# 3G4G.net
KiCad netlist of a schematic drawn in Altium Designer
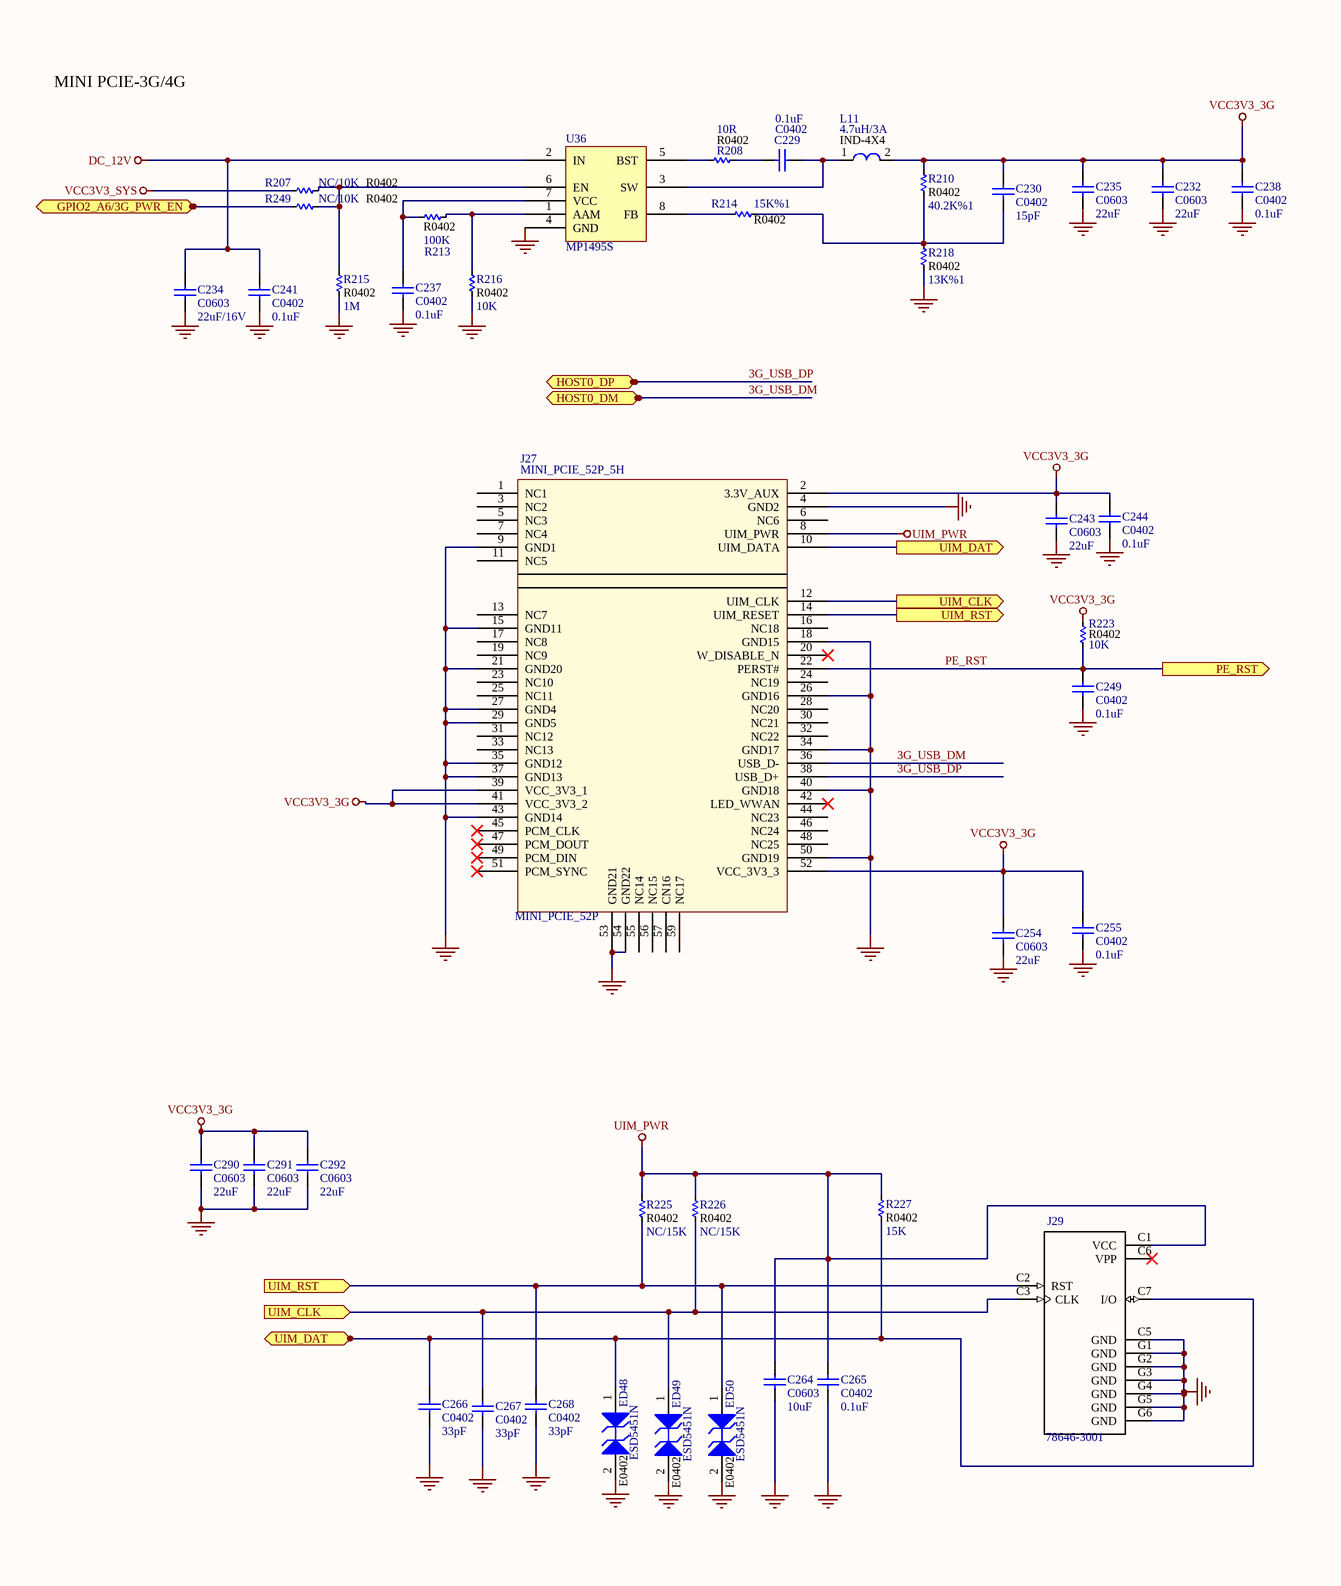
[diagram p0: 3G4G.SchDoc, left]
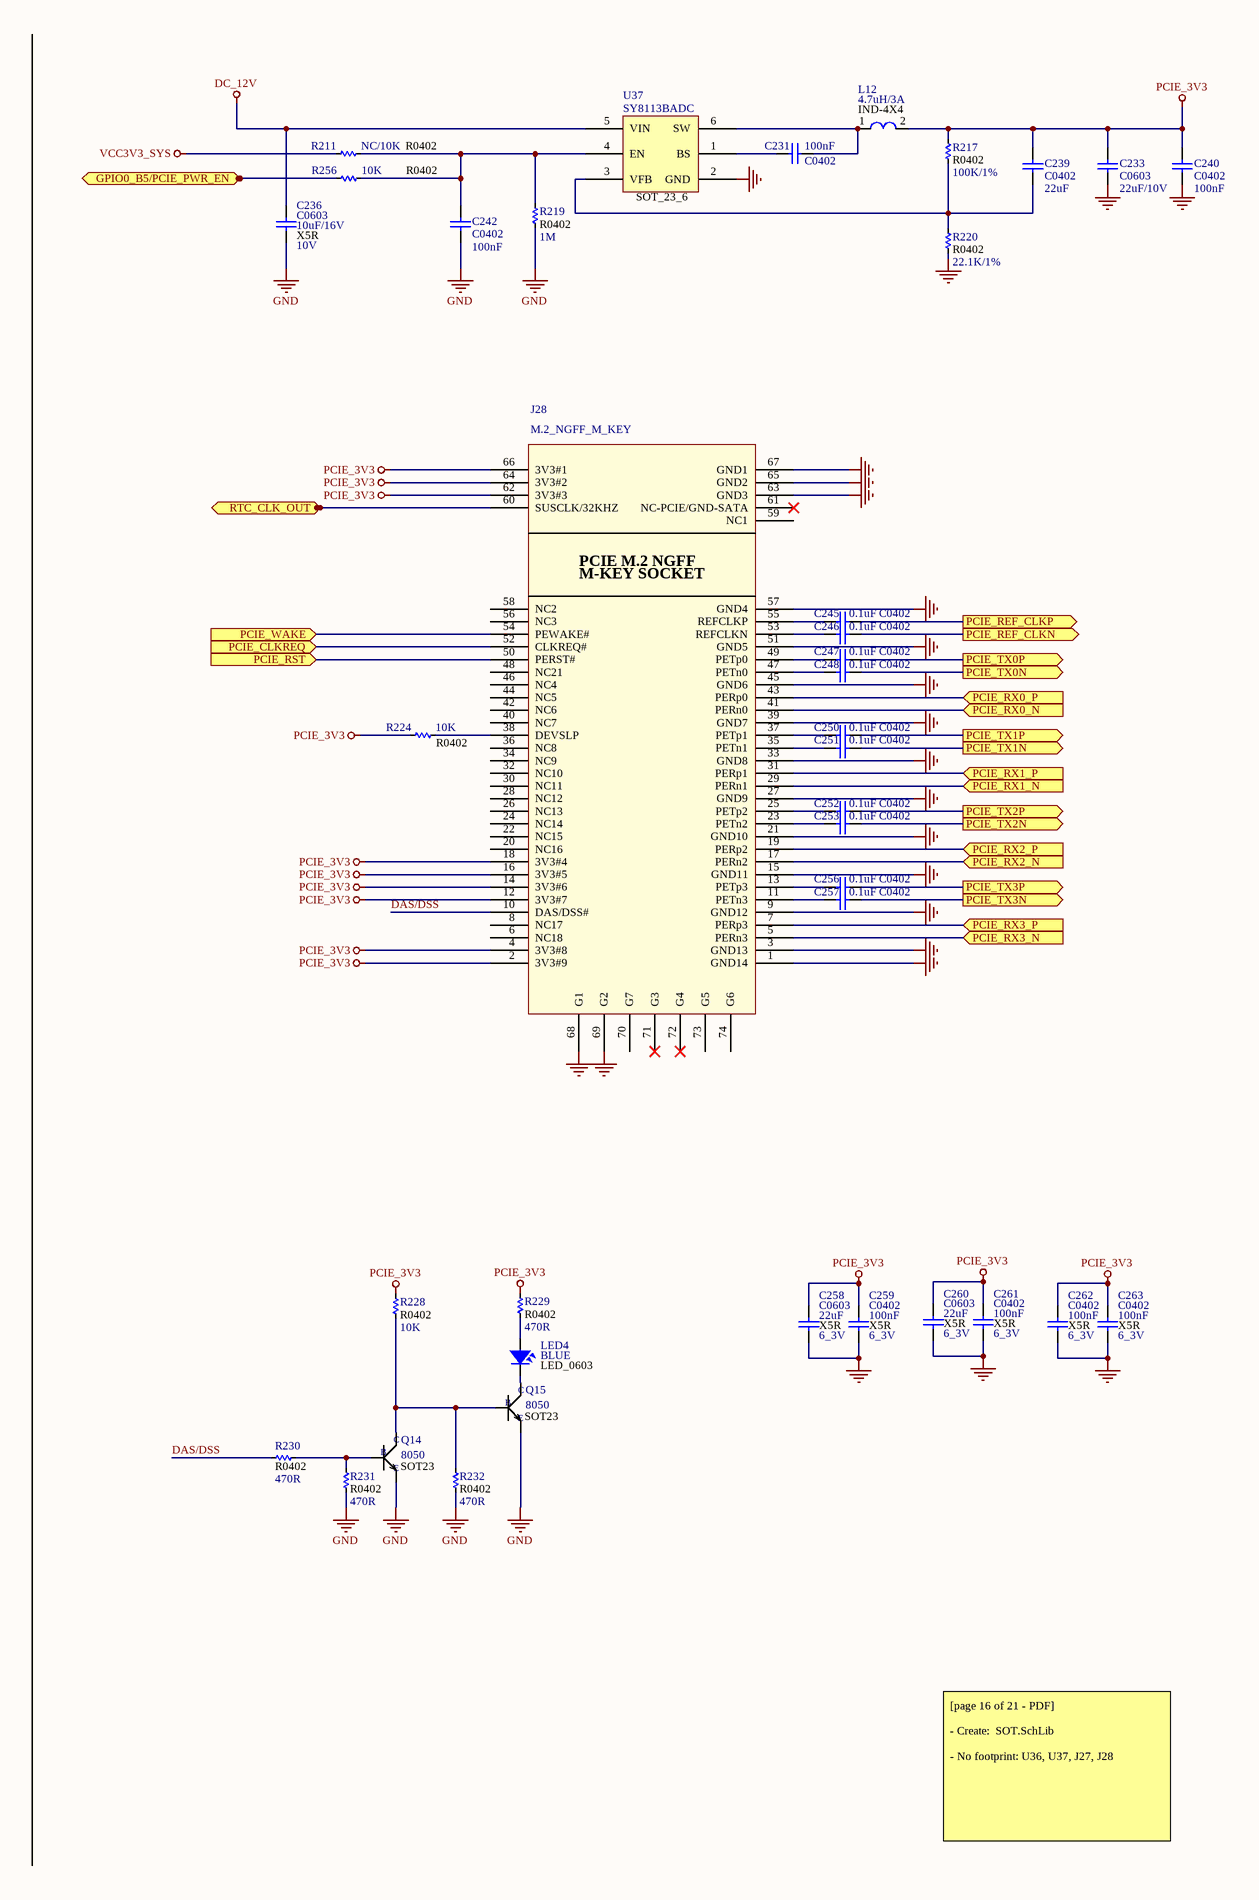
[diagram p1: 3G4G.SchDoc, right]

(export (version "E")
  (design (tool "Eeschema 10.0.6"))
  (components
    (comp (ref "C229")
      (value "C0402")
      (footprint "C 0402")
      (description "Capacitor")
      (fields (field (name "ALTIUM_VALUE") "0.1uF"))
      (libsource (lib "Miscellaneous Devices") (part "Cap"))
    )
    (comp (ref "C230")
      (value "C0402")
      (footprint "C 0402")
      (description "Capacitor")
      (fields (field (name "ALTIUM_VALUE") "15pF"))
      (libsource (lib "Miscellaneous Devices") (part "Cap"))
    )
    (comp (ref "C231")
      (value "C0402")
      (footprint "C 0402")
      (description "Capacitor")
      (fields (field (name "ALTIUM_VALUE") "100nF"))
      (libsource (lib "Miscellaneous Devices") (part "Cap"))
    )
    (comp (ref "C232")
      (value "C0603")
      (footprint "C 0603")
      (description "Capacitor")
      (fields (field (name "ALTIUM_VALUE") "22uF"))
      (libsource (lib "Miscellaneous Devices") (part "Cap"))
    )
    (comp (ref "C233")
      (value "C0603")
      (footprint "C 0603")
      (description "Capacitor")
      (fields (field (name "ALTIUM_VALUE") "22uF/10V"))
      (libsource (lib "Miscellaneous Devices") (part "Cap"))
    )
    (comp (ref "C234")
      (value "C0603")
      (footprint "C 0603")
      (description "Capacitor")
      (fields (field (name "ALTIUM_VALUE") "22uF/16V"))
      (libsource (lib "Miscellaneous Devices") (part "Cap"))
    )
    (comp (ref "C235")
      (value "C0603")
      (footprint "C 0603")
      (description "Capacitor")
      (fields (field (name "ALTIUM_VALUE") "22uF"))
      (libsource (lib "Miscellaneous Devices") (part "Cap"))
    )
    (comp (ref "C236")
      (value "C0603")
      (footprint "C 0603")
      (description "Capacitor")
      (fields
        (field (name "ALTIUM_VALUE") "10uF/16V")
        (field (name "ALTIUM_UNNAMED_1") "X5R")
        (field (name "ALTIUM_UNNAMED_2") "10V")
      )
      (libsource (lib "Miscellaneous Devices") (part "Cap"))
    )
    (comp (ref "C237")
      (value "C0402")
      (footprint "C 0402")
      (description "Capacitor")
      (fields (field (name "ALTIUM_VALUE") "0.1uF"))
      (libsource (lib "Miscellaneous Devices") (part "Cap"))
    )
    (comp (ref "C238")
      (value "C0402")
      (footprint "C 0402")
      (description "Capacitor")
      (fields (field (name "ALTIUM_VALUE") "0.1uF"))
      (libsource (lib "Miscellaneous Devices") (part "Cap"))
    )
    (comp (ref "C239")
      (value "C0402")
      (footprint "C 0402")
      (description "Capacitor")
      (fields (field (name "ALTIUM_VALUE") "22uF"))
      (libsource (lib "Miscellaneous Devices") (part "Cap"))
    )
    (comp (ref "C240")
      (value "C0402")
      (footprint "C 0402")
      (description "Capacitor")
      (fields (field (name "ALTIUM_VALUE") "100nF"))
      (libsource (lib "Miscellaneous Devices") (part "Cap"))
    )
    (comp (ref "C241")
      (value "C0402")
      (footprint "C 0402")
      (description "Capacitor")
      (fields (field (name "ALTIUM_VALUE") "0.1uF"))
      (libsource (lib "Miscellaneous Devices") (part "Cap"))
    )
    (comp (ref "C242")
      (value "C0402")
      (footprint "C 0402")
      (description "Capacitor")
      (fields (field (name "ALTIUM_VALUE") "100nF"))
      (libsource (lib "Miscellaneous Devices") (part "Cap"))
    )
    (comp (ref "C243")
      (value "C0603")
      (footprint "C 0603")
      (description "Capacitor")
      (fields (field (name "ALTIUM_VALUE") "22uF"))
      (libsource (lib "Miscellaneous Devices") (part "Cap"))
    )
    (comp (ref "C244")
      (value "C0402")
      (footprint "C 0402")
      (description "Capacitor")
      (fields (field (name "ALTIUM_VALUE") "0.1uF"))
      (libsource (lib "Miscellaneous Devices") (part "Cap"))
    )
    (comp (ref "C245")
      (value "C0402")
      (footprint "C 0402")
      (description "Capacitor")
      (fields (field (name "ALTIUM_VALUE") "0.1uF"))
      (libsource (lib "Miscellaneous Devices") (part "Cap"))
    )
    (comp (ref "C246")
      (value "C0402")
      (footprint "C 0402")
      (description "Capacitor")
      (fields (field (name "ALTIUM_VALUE") "0.1uF"))
      (libsource (lib "Miscellaneous Devices") (part "Cap"))
    )
    (comp (ref "C247")
      (value "C0402")
      (footprint "C 0402")
      (description "Capacitor")
      (fields (field (name "ALTIUM_VALUE") "0.1uF"))
      (libsource (lib "Miscellaneous Devices") (part "Cap"))
    )
    (comp (ref "C248")
      (value "C0402")
      (footprint "C 0402")
      (description "Capacitor")
      (fields (field (name "ALTIUM_VALUE") "0.1uF"))
      (libsource (lib "Miscellaneous Devices") (part "Cap"))
    )
    (comp (ref "C249")
      (value "C0402")
      (footprint "C 0402")
      (description "Capacitor")
      (fields (field (name "ALTIUM_VALUE") "0.1uF"))
      (libsource (lib "Miscellaneous Devices") (part "Cap"))
    )
    (comp (ref "C250")
      (value "C0402")
      (footprint "C 0402")
      (description "Capacitor")
      (fields (field (name "ALTIUM_VALUE") "0.1uF"))
      (libsource (lib "Miscellaneous Devices") (part "Cap"))
    )
    (comp (ref "C251")
      (value "C0402")
      (footprint "C 0402")
      (description "Capacitor")
      (fields (field (name "ALTIUM_VALUE") "0.1uF"))
      (libsource (lib "Miscellaneous Devices") (part "Cap"))
    )
    (comp (ref "C252")
      (value "C0402")
      (footprint "C 0402")
      (description "Capacitor")
      (fields (field (name "ALTIUM_VALUE") "0.1uF"))
      (libsource (lib "Miscellaneous Devices") (part "Cap"))
    )
    (comp (ref "C253")
      (value "C0402")
      (footprint "C 0402")
      (description "Capacitor")
      (fields (field (name "ALTIUM_VALUE") "0.1uF"))
      (libsource (lib "Miscellaneous Devices") (part "Cap"))
    )
    (comp (ref "C254")
      (value "C0603")
      (footprint "C 0603")
      (description "Capacitor")
      (fields (field (name "ALTIUM_VALUE") "22uF"))
      (libsource (lib "Miscellaneous Devices") (part "Cap"))
    )
    (comp (ref "C255")
      (value "C0402")
      (footprint "C 0402")
      (description "Capacitor")
      (fields (field (name "ALTIUM_VALUE") "0.1uF"))
      (libsource (lib "Miscellaneous Devices") (part "Cap"))
    )
    (comp (ref "C256")
      (value "C0402")
      (footprint "C 0402")
      (description "Capacitor")
      (fields (field (name "ALTIUM_VALUE") "0.1uF"))
      (libsource (lib "Miscellaneous Devices") (part "Cap"))
    )
    (comp (ref "C257")
      (value "C0402")
      (footprint "C 0402")
      (description "Capacitor")
      (fields (field (name "ALTIUM_VALUE") "0.1uF"))
      (libsource (lib "Miscellaneous Devices") (part "Cap"))
    )
    (comp (ref "C258")
      (value "C0603")
      (footprint "C 0603")
      (description "Capacitor")
      (fields
        (field (name "ALTIUM_VALUE") "22uF")
        (field (name "ALTIUM_UNNAMED_1") "X5R")
        (field (name "ALTIUM_UNNAMED_2") "6_3V")
      )
      (libsource (lib "Miscellaneous Devices") (part "Cap"))
    )
    (comp (ref "C259")
      (value "C0402")
      (footprint "C 0402")
      (description "Capacitor")
      (fields
        (field (name "ALTIUM_VALUE") "100nF")
        (field (name "ALTIUM_UNNAMED_1") "X5R")
        (field (name "ALTIUM_UNNAMED_2") "6_3V")
      )
      (libsource (lib "Miscellaneous Devices") (part "Cap"))
    )
    (comp (ref "C260")
      (value "C0603")
      (footprint "C 0603")
      (description "Capacitor")
      (fields
        (field (name "ALTIUM_VALUE") "22uF")
        (field (name "ALTIUM_UNNAMED_1") "X5R")
        (field (name "ALTIUM_UNNAMED_2") "6_3V")
      )
      (libsource (lib "Miscellaneous Devices") (part "Cap"))
    )
    (comp (ref "C261")
      (value "C0402")
      (footprint "C 0402")
      (description "Capacitor")
      (fields
        (field (name "ALTIUM_VALUE") "100nF")
        (field (name "ALTIUM_UNNAMED_1") "X5R")
        (field (name "ALTIUM_UNNAMED_2") "6_3V")
      )
      (libsource (lib "Miscellaneous Devices") (part "Cap"))
    )
    (comp (ref "C262")
      (value "C0402")
      (footprint "C 0402")
      (description "Capacitor")
      (fields
        (field (name "ALTIUM_VALUE") "100nF")
        (field (name "ALTIUM_UNNAMED_1") "X5R")
        (field (name "ALTIUM_UNNAMED_2") "6_3V")
      )
      (libsource (lib "Miscellaneous Devices") (part "Cap"))
    )
    (comp (ref "C263")
      (value "C0402")
      (footprint "C 0402")
      (description "Capacitor")
      (fields
        (field (name "ALTIUM_VALUE") "100nF")
        (field (name "ALTIUM_UNNAMED_1") "X5R")
        (field (name "ALTIUM_UNNAMED_2") "6_3V")
      )
      (libsource (lib "Miscellaneous Devices") (part "Cap"))
    )
    (comp (ref "C264")
      (value "C0603")
      (footprint "C 0603")
      (description "Capacitor")
      (fields (field (name "ALTIUM_VALUE") "10uF"))
      (libsource (lib "Miscellaneous Devices") (part "Cap"))
    )
    (comp (ref "C265")
      (value "C0402")
      (footprint "C 0402")
      (description "Capacitor")
      (fields (field (name "ALTIUM_VALUE") "0.1uF"))
      (libsource (lib "Miscellaneous Devices") (part "Cap"))
    )
    (comp (ref "C266")
      (value "C0402")
      (footprint "C 0402")
      (description "Capacitor")
      (fields (field (name "ALTIUM_VALUE") "33pF"))
      (libsource (lib "Miscellaneous Devices") (part "Cap"))
    )
    (comp (ref "C267")
      (value "C0402")
      (footprint "C 0402")
      (description "Capacitor")
      (fields (field (name "ALTIUM_VALUE") "33pF"))
      (libsource (lib "Miscellaneous Devices") (part "Cap"))
    )
    (comp (ref "C268")
      (value "C0402")
      (footprint "C 0402")
      (description "Capacitor")
      (fields (field (name "ALTIUM_VALUE") "33pF"))
      (libsource (lib "Miscellaneous Devices") (part "Cap"))
    )
    (comp (ref "C290")
      (value "C0603")
      (footprint "C 0603")
      (description "Capacitor")
      (fields (field (name "ALTIUM_VALUE") "22uF"))
      (libsource (lib "Miscellaneous Devices") (part "Cap"))
    )
    (comp (ref "C291")
      (value "C0603")
      (footprint "C 0603")
      (description "Capacitor")
      (fields (field (name "ALTIUM_VALUE") "22uF"))
      (libsource (lib "Miscellaneous Devices") (part "Cap"))
    )
    (comp (ref "C292")
      (value "C0603")
      (footprint "C 0603")
      (description "Capacitor")
      (fields (field (name "ALTIUM_VALUE") "22uF"))
      (libsource (lib "Miscellaneous Devices") (part "Cap"))
    )
    (comp (ref "ED48")
      (value "ESD5451N")
      (footprint "DFN1006-2L")
      (description "600 W Peak Power Zener Transient Voltage Suppressor, Bidirectional, 2-Pin SMB, Tape and Reel")
      (fields
        (field (name "MANUFACTURER") "On Semiconductor")
        (field (name "PARTNUMBER") "1SMB54CAT3")
        (field (name "SIZE") "E0402")
      )
      (libsource (lib "ON Semi Transient Voltage Suppressors (TVS)") (part "1SMB54CAT3"))
    )
    (comp (ref "ED49")
      (value "ESD5451N")
      (footprint "DFN1006-2L")
      (description "600 W Peak Power Zener Transient Voltage Suppressor, Bidirectional, 2-Pin SMB, Tape and Reel")
      (fields
        (field (name "MANUFACTURER") "On Semiconductor")
        (field (name "PARTNUMBER") "1SMB54CAT3")
        (field (name "SIZE") "E0402")
      )
      (libsource (lib "ON Semi Transient Voltage Suppressors (TVS)") (part "1SMB54CAT3"))
    )
    (comp (ref "ED50")
      (value "ESD5451N")
      (footprint "DFN1006-2L")
      (description "600 W Peak Power Zener Transient Voltage Suppressor, Bidirectional, 2-Pin SMB, Tape and Reel")
      (fields
        (field (name "MANUFACTURER") "On Semiconductor")
        (field (name "PARTNUMBER") "1SMB54CAT3")
        (field (name "SIZE") "E0402")
      )
      (libsource (lib "ON Semi Transient Voltage Suppressors (TVS)") (part "1SMB54CAT3"))
    )
    (comp (ref "J27")
      (value "MINI_PCIE_52P_5H")
      (footprint "MINI_PCIE_52PIN")
      (fields (field (name "ALTIUM_UNNAMED_1") "MINI_PCIE_52P"))
      (libsource (lib "SOT") (part "MINI_PCIE_52P_5H"))
    )
    (comp (ref "J28")
      (value "M.2_NGFF_M_KEY")
      (footprint "*CONN_1-2199230-5_1-2199230-5(Primary)")
      (libsource (lib "SOT") (part "M.2_NGFF_M_KEY"))
    )
    (comp (ref "J29")
      (value "78646-3001")
      (footprint "*CONN_78646-3001_78646-3001(Primary)")
      (description "Conn Micro SIM Card SKT 6 POS 2.54mm Solder RA SMD 0.5A/Contact Embossed T/R")
      (fields (field (name "MF") "Molex"))
      (libsource (lib "78646-3001") (part "78646-3001"))
    )
    (comp (ref "L11")
      (value "4.7uH/3A")
      (footprint "L-SMD-M-7.3x4.5")
      (fields
        (field (name "PARTNO") "78477010")
        (field (name "MANUFACTURER") "Wurth Elektronik")
        (field (name "ALTIUM_UNNAMED_1") "IND-4X4")
      )
      (libsource (lib "LIBRARY") (part "L-SMD-1"))
    )
    (comp (ref "L12")
      (value "4.7uH/3A")
      (footprint "L-SMD-M-7.3x4.5")
      (fields
        (field (name "PARTNO") "78477010")
        (field (name "MANUFACTURER") "Wurth Elektronik")
        (field (name "ALTIUM_UNNAMED_1") "IND-4X4")
      )
      (libsource (lib "LIBRARY") (part "L-SMD-1"))
    )
    (comp (ref "LED4")
      (value "LED SMD")
      (footprint "SM-LED-0805-Blue")
      (fields (field (name "PACKAGE") "LED_0603") (field (name "COLOR") "BLUE"))
      (libsource (lib "syhaunguyen") (part "LED-SMD-0805"))
    )
    (comp (ref "Q14")
      (value "8050")
      (footprint "*SOT-23")
      (fields
        (field (name "MF") "Recom Power")
        (field (name "MP") "S8050")
        (field (name "ALTIUM_UNNAMED_1") "SOT23")
      )
      (libsource (lib "SMD-TRANSISTORS-NPN-25V-500MW_SOT-23_") (part "SMD-TRANSISTORS-NPN-25V-500MW(SOT-23)"))
    )
    (comp (ref "Q15")
      (value "8050")
      (footprint "*SOT-23")
      (fields
        (field (name "MF") "Recom Power")
        (field (name "MP") "S8050")
        (field (name "ALTIUM_UNNAMED_1") "SOT23")
      )
      (libsource (lib "SMD-TRANSISTORS-NPN-25V-500MW_SOT-23_") (part "SMD-TRANSISTORS-NPN-25V-500MW(SOT-23)"))
    )
    (comp (ref "R207")
      (value "R0402")
      (footprint "R 0402")
      (description "Resistor")
      (fields (field (name "MANUFACTURER") "Generic Components") (field (name "ALTIUM_VALUE") "NC/10K"))
      (libsource (lib "LIBRARY") (part "Res-SMD"))
    )
    (comp (ref "R208")
      (value "R0402")
      (footprint "R 0402")
      (description "Resistor")
      (fields (field (name "MANUFACTURER") "Generic Components") (field (name "ALTIUM_VALUE") "10R"))
      (libsource (lib "LIBRARY") (part "Res-SMD"))
    )
    (comp (ref "R210")
      (value "R0402")
      (footprint "R 0402")
      (description "Resistor")
      (fields (field (name "MANUFACTURER") "Generic Components") (field (name "ALTIUM_VALUE") "40.2K%1"))
      (libsource (lib "LIBRARY") (part "Res-SMD"))
    )
    (comp (ref "R211")
      (value "R0402")
      (footprint "R 0402")
      (description "Resistor")
      (fields (field (name "MANUFACTURER") "Generic Components") (field (name "ALTIUM_VALUE") "NC/10K"))
      (libsource (lib "LIBRARY") (part "Res-SMD"))
    )
    (comp (ref "R213")
      (value "R0402")
      (footprint "R 0402")
      (description "Resistor")
      (fields (field (name "MANUFACTURER") "Generic Components") (field (name "ALTIUM_VALUE") "100K"))
      (libsource (lib "LIBRARY") (part "Res-SMD"))
    )
    (comp (ref "R214")
      (value "R0402")
      (footprint "R 0402")
      (description "Resistor")
      (fields (field (name "MANUFACTURER") "Generic Components") (field (name "ALTIUM_VALUE") "15K%1"))
      (libsource (lib "LIBRARY") (part "Res-SMD"))
    )
    (comp (ref "R215")
      (value "R0402")
      (footprint "R 0402")
      (description "Resistor")
      (fields (field (name "MANUFACTURER") "Generic Components") (field (name "ALTIUM_VALUE") "1M"))
      (libsource (lib "LIBRARY") (part "Res-SMD"))
    )
    (comp (ref "R216")
      (value "R0402")
      (footprint "R 0402")
      (description "Resistor")
      (fields (field (name "MANUFACTURER") "Generic Components") (field (name "ALTIUM_VALUE") "10K"))
      (libsource (lib "LIBRARY") (part "Res-SMD"))
    )
    (comp (ref "R217")
      (value "R0402")
      (footprint "R 0402")
      (description "Resistor")
      (fields (field (name "MANUFACTURER") "Generic Components") (field (name "ALTIUM_VALUE") "100K/1%"))
      (libsource (lib "LIBRARY") (part "Res-SMD"))
    )
    (comp (ref "R218")
      (value "R0402")
      (footprint "R 0402")
      (description "Resistor")
      (fields (field (name "MANUFACTURER") "Generic Components") (field (name "ALTIUM_VALUE") "13K%1"))
      (libsource (lib "LIBRARY") (part "Res-SMD"))
    )
    (comp (ref "R219")
      (value "R0402")
      (footprint "R 0402")
      (description "Resistor")
      (fields (field (name "MANUFACTURER") "Generic Components") (field (name "ALTIUM_VALUE") "1M"))
      (libsource (lib "LIBRARY") (part "Res-SMD"))
    )
    (comp (ref "R220")
      (value "R0402")
      (footprint "R 0402")
      (description "Resistor")
      (fields (field (name "MANUFACTURER") "Generic Components") (field (name "ALTIUM_VALUE") "22.1K/1%"))
      (libsource (lib "LIBRARY") (part "Res-SMD"))
    )
    (comp (ref "R223")
      (value "R0402")
      (footprint "R 0402")
      (description "Resistor")
      (fields (field (name "MANUFACTURER") "Generic Components") (field (name "ALTIUM_VALUE") "10K"))
      (libsource (lib "LIBRARY") (part "Res-SMD"))
    )
    (comp (ref "R224")
      (value "R0402")
      (footprint "R 0402")
      (description "Resistor")
      (fields (field (name "MANUFACTURER") "Generic Components") (field (name "ALTIUM_VALUE") "10K"))
      (libsource (lib "LIBRARY") (part "Res-SMD"))
    )
    (comp (ref "R225")
      (value "R0402")
      (footprint "R 0402")
      (description "Resistor")
      (fields (field (name "MANUFACTURER") "Generic Components") (field (name "ALTIUM_VALUE") "NC/15K"))
      (libsource (lib "LIBRARY") (part "Res-SMD"))
    )
    (comp (ref "R226")
      (value "R0402")
      (footprint "R 0402")
      (description "Resistor")
      (fields (field (name "MANUFACTURER") "Generic Components") (field (name "ALTIUM_VALUE") "NC/15K"))
      (libsource (lib "LIBRARY") (part "Res-SMD"))
    )
    (comp (ref "R227")
      (value "R0402")
      (footprint "R 0402")
      (description "Resistor")
      (fields (field (name "MANUFACTURER") "Generic Components") (field (name "ALTIUM_VALUE") "15K"))
      (libsource (lib "LIBRARY") (part "Res-SMD"))
    )
    (comp (ref "R228")
      (value "R0402")
      (footprint "R 0402")
      (description "Resistor")
      (fields (field (name "MANUFACTURER") "Generic Components") (field (name "ALTIUM_VALUE") "10K"))
      (libsource (lib "LIBRARY") (part "Res-SMD"))
    )
    (comp (ref "R229")
      (value "R0402")
      (footprint "R 0402")
      (description "Resistor")
      (fields (field (name "MANUFACTURER") "Generic Components") (field (name "ALTIUM_VALUE") "470R"))
      (libsource (lib "LIBRARY") (part "Res-SMD"))
    )
    (comp (ref "R230")
      (value "R0402")
      (footprint "R 0402")
      (description "Resistor")
      (fields (field (name "MANUFACTURER") "Generic Components") (field (name "ALTIUM_VALUE") "470R"))
      (libsource (lib "LIBRARY") (part "Res-SMD"))
    )
    (comp (ref "R231")
      (value "R0402")
      (footprint "R 0402")
      (description "Resistor")
      (fields (field (name "MANUFACTURER") "Generic Components") (field (name "ALTIUM_VALUE") "470R"))
      (libsource (lib "LIBRARY") (part "Res-SMD"))
    )
    (comp (ref "R232")
      (value "R0402")
      (footprint "R 0402")
      (description "Resistor")
      (fields (field (name "MANUFACTURER") "Generic Components") (field (name "ALTIUM_VALUE") "470R"))
      (libsource (lib "LIBRARY") (part "Res-SMD"))
    )
    (comp (ref "R249")
      (value "R0402")
      (footprint "R 0402")
      (description "Resistor")
      (fields (field (name "MANUFACTURER") "Generic Components") (field (name "ALTIUM_VALUE") "NC/10K"))
      (libsource (lib "LIBRARY") (part "Res-SMD"))
    )
    (comp (ref "R256")
      (value "R0402")
      (footprint "R 0402")
      (description "Resistor")
      (fields (field (name "MANUFACTURER") "Generic Components") (field (name "ALTIUM_VALUE") "10K"))
      (libsource (lib "LIBRARY") (part "Res-SMD"))
    )
    (comp (ref "U36") (value "MP1495S") (footprint "SOT:TSOT-23-8") (libsource (lib "SOT") (part "MP1495S")))
    (comp (ref "U37")
      (value "SOT-23-6_SY8113BADC")
      (footprint "SOT:SOT-23-6")
      (description "Switching Voltage Regulators 17 Vin,3A Sync SD Reg")
      (fields
        (field (name "MANUFACTURER") "Texas Instruments")
        (field (name "MANUFACTURER PART NUMBER") "TPS563200DDCR")
      )
      (libsource (lib "SOT") (part "SOT-23-6_SY8113BADC"))
    )
  )
  (nets
    (net (code "1") (name "/3G_USB_DM") (class "Default")
      (node (ref "J27") (pin "36") (pinfunction "USB_D-_36") (pintype "passive"))
    )
    (net (code "2") (name "/3G_USB_DP") (class "Default")
      (node (ref "J27") (pin "38") (pinfunction "USB_D+_38") (pintype "passive"))
    )
    (net (code "3") (name "/DAS{slash}DSS") (class "Default")
      (node (ref "J28") (pin "10") (pinfunction "DAS/DSS#_10") (pintype "passive"))
      (node (ref "R230") (pin "2") (pinfunction "2_2") (pintype "passive"))
    )
    (net (code "4") (name "/GPIO0_B5{slash}PCIE_PWR_EN") (class "Default")
      (node (ref "R256") (pin "2") (pinfunction "2_2") (pintype "passive"))
    )
    (net (code "5") (name "/GPIO2_A6{slash}3G_PWR_EN") (class "Default")
      (node (ref "R249") (pin "2") (pinfunction "2_2") (pintype "passive"))
    )
    (net (code "6") (name "/PCIE_CLKREQ") (class "Default")
      (node (ref "J28") (pin "52") (pinfunction "CLKREQ#_52") (pintype "passive"))
    )
    (net (code "7") (name "/PCIE_REF_CLKN") (class "Default")
      (node (ref "C246") (pin "1") (pinfunction "1_1") (pintype "passive"))
    )
    (net (code "8") (name "/PCIE_REF_CLKP") (class "Default")
      (node (ref "C245") (pin "1") (pinfunction "1_1") (pintype "passive"))
    )
    (net (code "9") (name "/PCIE_RST") (class "Default")
      (node (ref "J28") (pin "50") (pinfunction "PERST#_50") (pintype "passive"))
    )
    (net (code "10") (name "/PCIE_RX0_N") (class "Default")
      (node (ref "J28") (pin "41") (pinfunction "PERn0_41") (pintype "passive"))
    )
    (net (code "11") (name "/PCIE_RX0_P") (class "Default")
      (node (ref "J28") (pin "43") (pinfunction "PERp0_43") (pintype "passive"))
    )
    (net (code "12") (name "/PCIE_RX1_N") (class "Default")
      (node (ref "J28") (pin "29") (pinfunction "PERn1_29") (pintype "passive"))
    )
    (net (code "13") (name "/PCIE_RX1_P") (class "Default")
      (node (ref "J28") (pin "31") (pinfunction "PERp1_31") (pintype "passive"))
    )
    (net (code "14") (name "/PCIE_RX2_N") (class "Default")
      (node (ref "J28") (pin "17") (pinfunction "PERn2_17") (pintype "passive"))
    )
    (net (code "15") (name "/PCIE_RX2_P") (class "Default")
      (node (ref "J28") (pin "19") (pinfunction "PERp2_19") (pintype "passive"))
    )
    (net (code "16") (name "/PCIE_RX3_N") (class "Default")
      (node (ref "J28") (pin "5") (pinfunction "PERn3_5") (pintype "passive"))
    )
    (net (code "17") (name "/PCIE_RX3_P") (class "Default")
      (node (ref "J28") (pin "7") (pinfunction "PERp3_7") (pintype "passive"))
    )
    (net (code "18") (name "/PCIE_TX0N") (class "Default")
      (node (ref "C248") (pin "1") (pinfunction "1_1") (pintype "passive"))
    )
    (net (code "19") (name "/PCIE_TX0P") (class "Default")
      (node (ref "C247") (pin "1") (pinfunction "1_1") (pintype "passive"))
    )
    (net (code "20") (name "/PCIE_TX1N") (class "Default")
      (node (ref "C251") (pin "1") (pinfunction "1_1") (pintype "passive"))
    )
    (net (code "21") (name "/PCIE_TX1P") (class "Default")
      (node (ref "C250") (pin "1") (pinfunction "1_1") (pintype "passive"))
    )
    (net (code "22") (name "/PCIE_TX2N") (class "Default")
      (node (ref "C253") (pin "1") (pinfunction "1_1") (pintype "passive"))
    )
    (net (code "23") (name "/PCIE_TX2P") (class "Default")
      (node (ref "C252") (pin "1") (pinfunction "1_1") (pintype "passive"))
    )
    (net (code "24") (name "/PCIE_TX3N") (class "Default")
      (node (ref "C257") (pin "1") (pinfunction "1_1") (pintype "passive"))
    )
    (net (code "25") (name "/PCIE_TX3P") (class "Default")
      (node (ref "C256") (pin "1") (pinfunction "1_1") (pintype "passive"))
    )
    (net (code "26") (name "/PCIE_WAKE") (class "Default")
      (node (ref "J28") (pin "54") (pinfunction "PEWAKE#_54") (pintype "passive"))
    )
    (net (code "27") (name "/PE_RST") (class "Default")
      (node (ref "C249") (pin "2") (pinfunction "2_2") (pintype "passive"))
      (node (ref "J27") (pin "22") (pinfunction "PERST#_22") (pintype "passive"))
      (node (ref "R223") (pin "1") (pinfunction "1_1") (pintype "passive"))
    )
    (net (code "28") (name "/RTC_CLK_OUT") (class "Default")
      (node (ref "J28") (pin "60") (pinfunction "SUSCLK/32KHZ_60") (pintype "passive"))
    )
    (net (code "29") (name "/UIM_CLK") (class "Default")
      (node (ref "C267") (pin "2") (pinfunction "2_2") (pintype "passive"))
      (node (ref "ED49") (pin "1") (pinfunction "A1_1") (pintype "passive"))
      (node (ref "J27") (pin "12") (pinfunction "UIM_CLK_12") (pintype "passive"))
      (node (ref "J29") (pin "C3") (pinfunction "CLK_C3") (pintype "input"))
      (node (ref "R226") (pin "1") (pinfunction "1_1") (pintype "passive"))
    )
    (net (code "30") (name "/UIM_DAT") (class "Default")
      (node (ref "C266") (pin "2") (pinfunction "2_2") (pintype "passive"))
      (node (ref "ED48") (pin "1") (pinfunction "A1_1") (pintype "passive"))
      (node (ref "J27") (pin "10") (pinfunction "UIM_DATA_10") (pintype "passive"))
      (node (ref "J29") (pin "C7") (pinfunction "I/O_C7") (pintype "bidirectional"))
      (node (ref "R227") (pin "1") (pinfunction "1_1") (pintype "passive"))
    )
    (net (code "31") (name "/UIM_RST") (class "Default")
      (node (ref "C268") (pin "2") (pinfunction "2_2") (pintype "passive"))
      (node (ref "ED50") (pin "1") (pinfunction "A1_1") (pintype "passive"))
      (node (ref "J27") (pin "14") (pinfunction "UIM_RESET_14") (pintype "passive"))
      (node (ref "J29") (pin "C2") (pinfunction "RST_C2") (pintype "input"))
      (node (ref "R225") (pin "1") (pinfunction "1_1") (pintype "passive"))
    )
    (net (code "32") (name "DC_12V") (class "Default")
      (node (ref "C234") (pin "1") (pinfunction "1_1") (pintype "passive"))
      (node (ref "C236") (pin "1") (pinfunction "1_1") (pintype "passive"))
      (node (ref "C241") (pin "1") (pinfunction "1_1") (pintype "passive"))
      (node (ref "U36") (pin "2") (pinfunction "IN_2") (pintype "passive"))
      (node (ref "U37") (pin "5") (pinfunction "VIN_5") (pintype "passive"))
    )
    (net (code "33") (name "GND") (class "Default")
      (node (ref "C232") (pin "1") (pinfunction "1_1") (pintype "passive"))
      (node (ref "C233") (pin "1") (pinfunction "1_1") (pintype "passive"))
      (node (ref "C234") (pin "2") (pinfunction "2_2") (pintype "passive"))
      (node (ref "C235") (pin "1") (pinfunction "1_1") (pintype "passive"))
      (node (ref "C236") (pin "2") (pinfunction "2_2") (pintype "passive"))
      (node (ref "C237") (pin "2") (pinfunction "2_2") (pintype "passive"))
      (node (ref "C238") (pin "1") (pinfunction "1_1") (pintype "passive"))
      (node (ref "C240") (pin "1") (pinfunction "1_1") (pintype "passive"))
      (node (ref "C241") (pin "2") (pinfunction "2_2") (pintype "passive"))
      (node (ref "C242") (pin "2") (pinfunction "2_2") (pintype "passive"))
      (node (ref "C243") (pin "1") (pinfunction "1_1") (pintype "passive"))
      (node (ref "C244") (pin "1") (pinfunction "1_1") (pintype "passive"))
      (node (ref "C249") (pin "1") (pinfunction "1_1") (pintype "passive"))
      (node (ref "C254") (pin "1") (pinfunction "1_1") (pintype "passive"))
      (node (ref "C255") (pin "1") (pinfunction "1_1") (pintype "passive"))
      (node (ref "C258") (pin "1") (pinfunction "1_1") (pintype "passive"))
      (node (ref "C259") (pin "1") (pinfunction "1_1") (pintype "passive"))
      (node (ref "C260") (pin "1") (pinfunction "1_1") (pintype "passive"))
      (node (ref "C261") (pin "1") (pinfunction "1_1") (pintype "passive"))
      (node (ref "C262") (pin "1") (pinfunction "1_1") (pintype "passive"))
      (node (ref "C263") (pin "1") (pinfunction "1_1") (pintype "passive"))
      (node (ref "C264") (pin "1") (pinfunction "1_1") (pintype "passive"))
      (node (ref "C265") (pin "1") (pinfunction "1_1") (pintype "passive"))
      (node (ref "C266") (pin "1") (pinfunction "1_1") (pintype "passive"))
      (node (ref "C267") (pin "1") (pinfunction "1_1") (pintype "passive"))
      (node (ref "C268") (pin "1") (pinfunction "1_1") (pintype "passive"))
      (node (ref "C290") (pin "1") (pinfunction "1_1") (pintype "passive"))
      (node (ref "C291") (pin "1") (pinfunction "1_1") (pintype "passive"))
      (node (ref "C292") (pin "1") (pinfunction "1_1") (pintype "passive"))
      (node (ref "ED48") (pin "2") (pinfunction "A2_2") (pintype "passive"))
      (node (ref "ED49") (pin "2") (pinfunction "A2_2") (pintype "passive"))
      (node (ref "ED50") (pin "2") (pinfunction "A2_2") (pintype "passive"))
      (node (ref "J27") (pin "15") (pinfunction "GND11_15") (pintype "passive"))
      (node (ref "J27") (pin "18") (pinfunction "GND15_18") (pintype "passive"))
      (node (ref "J27") (pin "21") (pinfunction "GND20_21") (pintype "passive"))
      (node (ref "J27") (pin "26") (pinfunction "GND16_26") (pintype "passive"))
      (node (ref "J27") (pin "27") (pinfunction "GND4_27") (pintype "passive"))
      (node (ref "J27") (pin "29") (pinfunction "GND5_29") (pintype "passive"))
      (node (ref "J27") (pin "34") (pinfunction "GND17_34") (pintype "passive"))
      (node (ref "J27") (pin "35") (pinfunction "GND12_35") (pintype "passive"))
      (node (ref "J27") (pin "37") (pinfunction "GND13_37") (pintype "passive"))
      (node (ref "J27") (pin "4") (pinfunction "GND2_4") (pintype "passive"))
      (node (ref "J27") (pin "40") (pinfunction "GND18_40") (pintype "passive"))
      (node (ref "J27") (pin "43") (pinfunction "GND14_43") (pintype "passive"))
      (node (ref "J27") (pin "50") (pinfunction "GND19_50") (pintype "passive"))
      (node (ref "J27") (pin "53") (pinfunction "GND21_53") (pintype "passive"))
      (node (ref "J27") (pin "54") (pinfunction "GND22_54") (pintype "passive"))
      (node (ref "J27") (pin "9") (pinfunction "GND1_9") (pintype "passive"))
      (node (ref "J28") (pin "1") (pinfunction "GND14_1") (pintype "passive"))
      (node (ref "J28") (pin "15") (pinfunction "GND11_15") (pintype "passive"))
      (node (ref "J28") (pin "21") (pinfunction "GND10_21") (pintype "passive"))
      (node (ref "J28") (pin "27") (pinfunction "GND9_27") (pintype "passive"))
      (node (ref "J28") (pin "3") (pinfunction "GND13_3") (pintype "passive"))
      (node (ref "J28") (pin "33") (pinfunction "GND8_33") (pintype "passive"))
      (node (ref "J28") (pin "39") (pinfunction "GND7_39") (pintype "passive"))
      (node (ref "J28") (pin "45") (pinfunction "GND6_45") (pintype "passive"))
      (node (ref "J28") (pin "51") (pinfunction "GND5_51") (pintype "passive"))
      (node (ref "J28") (pin "57") (pinfunction "GND4_57") (pintype "passive"))
      (node (ref "J28") (pin "63") (pinfunction "GND3_63") (pintype "passive"))
      (node (ref "J28") (pin "65") (pinfunction "GND2_65") (pintype "passive"))
      (node (ref "J28") (pin "67") (pinfunction "GND1_67") (pintype "passive"))
      (node (ref "J28") (pin "68") (pinfunction "G1_68") (pintype "passive"))
      (node (ref "J28") (pin "69") (pinfunction "G2_69") (pintype "passive"))
      (node (ref "J28") (pin "9") (pinfunction "GND12_9") (pintype "passive"))
      (node (ref "J29") (pin "C5") (pinfunction "GND_C5") (pintype "power_in"))
      (node (ref "J29") (pin "G1") (pinfunction "GND_G1") (pintype "power_in"))
      (node (ref "J29") (pin "G2") (pinfunction "GND_G2") (pintype "power_in"))
      (node (ref "J29") (pin "G3") (pinfunction "GND_G3") (pintype "power_in"))
      (node (ref "J29") (pin "G4") (pinfunction "GND_G4") (pintype "power_in"))
      (node (ref "J29") (pin "G5") (pinfunction "GND_G5") (pintype "power_in"))
      (node (ref "J29") (pin "G6") (pinfunction "GND_G6") (pintype "power_in"))
      (node (ref "Q14") (pin "2") (pinfunction "E_2") (pintype "passive"))
      (node (ref "Q15") (pin "2") (pinfunction "E_2") (pintype "passive"))
      (node (ref "R215") (pin "1") (pinfunction "1_1") (pintype "passive"))
      (node (ref "R216") (pin "1") (pinfunction "1_1") (pintype "passive"))
      (node (ref "R218") (pin "1") (pinfunction "1_1") (pintype "passive"))
      (node (ref "R219") (pin "2") (pinfunction "2_2") (pintype "passive"))
      (node (ref "R220") (pin "1") (pinfunction "1_1") (pintype "passive"))
      (node (ref "R231") (pin "2") (pinfunction "2_2") (pintype "passive"))
      (node (ref "R232") (pin "2") (pinfunction "2_2") (pintype "passive"))
      (node (ref "U36") (pin "4") (pinfunction "GND_4") (pintype "passive"))
      (node (ref "U37") (pin "2") (pinfunction "GND_2") (pintype "passive"))
    )
    (net (code "34") (name "Net-(C229-Pad1)") (class "Default")
      (node (ref "C229") (pin "1") (pinfunction "1_1") (pintype "passive"))
      (node (ref "R208") (pin "2") (pinfunction "2_2") (pintype "passive"))
    )
    (net (code "35") (name "Net-(C230-Pad1)") (class "Default")
      (node (ref "C230") (pin "1") (pinfunction "1_1") (pintype "passive"))
      (node (ref "R210") (pin "1") (pinfunction "1_1") (pintype "passive"))
      (node (ref "R214") (pin "2") (pinfunction "2_2") (pintype "passive"))
      (node (ref "R218") (pin "2") (pinfunction "2_2") (pintype "passive"))
    )
    (net (code "36") (name "Net-(J28-DEVSLP)") (class "Default")
      (node (ref "J28") (pin "38") (pinfunction "DEVSLP_38") (pintype "passive"))
      (node (ref "R224") (pin "1") (pinfunction "1_1") (pintype "passive"))
    )
    (net (code "37") (name "Net-(J28-PETn0)") (class "Default")
      (node (ref "C248") (pin "2") (pinfunction "2_2") (pintype "passive"))
      (node (ref "J28") (pin "47") (pinfunction "PETn0_47") (pintype "passive"))
    )
    (net (code "38") (name "Net-(J28-PETn1)") (class "Default")
      (node (ref "C251") (pin "2") (pinfunction "2_2") (pintype "passive"))
      (node (ref "J28") (pin "35") (pinfunction "PETn1_35") (pintype "passive"))
    )
    (net (code "39") (name "Net-(J28-PETn2)") (class "Default")
      (node (ref "C253") (pin "2") (pinfunction "2_2") (pintype "passive"))
      (node (ref "J28") (pin "23") (pinfunction "PETn2_23") (pintype "passive"))
    )
    (net (code "40") (name "Net-(J28-PETn3)") (class "Default")
      (node (ref "C257") (pin "2") (pinfunction "2_2") (pintype "passive"))
      (node (ref "J28") (pin "11") (pinfunction "PETn3_11") (pintype "passive"))
    )
    (net (code "41") (name "Net-(J28-PETp0)") (class "Default")
      (node (ref "C247") (pin "2") (pinfunction "2_2") (pintype "passive"))
      (node (ref "J28") (pin "49") (pinfunction "PETp0_49") (pintype "passive"))
    )
    (net (code "42") (name "Net-(J28-PETp1)") (class "Default")
      (node (ref "C250") (pin "2") (pinfunction "2_2") (pintype "passive"))
      (node (ref "J28") (pin "37") (pinfunction "PETp1_37") (pintype "passive"))
    )
    (net (code "43") (name "Net-(J28-PETp2)") (class "Default")
      (node (ref "C252") (pin "2") (pinfunction "2_2") (pintype "passive"))
      (node (ref "J28") (pin "25") (pinfunction "PETp2_25") (pintype "passive"))
    )
    (net (code "44") (name "Net-(J28-PETp3)") (class "Default")
      (node (ref "C256") (pin "2") (pinfunction "2_2") (pintype "passive"))
      (node (ref "J28") (pin "13") (pinfunction "PETp3_13") (pintype "passive"))
    )
    (net (code "45") (name "Net-(J28-REFCLKN)") (class "Default")
      (node (ref "C246") (pin "2") (pinfunction "2_2") (pintype "passive"))
      (node (ref "J28") (pin "53") (pinfunction "REFCLKN_53") (pintype "passive"))
    )
    (net (code "46") (name "Net-(J28-REFCLKP)") (class "Default")
      (node (ref "C245") (pin "2") (pinfunction "2_2") (pintype "passive"))
      (node (ref "J28") (pin "55") (pinfunction "REFCLKP_55") (pintype "passive"))
    )
    (net (code "47") (name "Net-(LED4-Pad1)") (class "Default")
      (node (ref "LED4") (pin "1") (pinfunction "1_1") (pintype "passive"))
      (node (ref "R229") (pin "1") (pinfunction "1_1") (pintype "passive"))
    )
    (net (code "48") (name "Net-(Q14-B)") (class "Default")
      (node (ref "Q14") (pin "1") (pinfunction "B_1") (pintype "passive"))
      (node (ref "R230") (pin "1") (pinfunction "1_1") (pintype "passive"))
      (node (ref "R231") (pin "1") (pinfunction "1_1") (pintype "passive"))
    )
    (net (code "49") (name "Net-(Q14-C)") (class "Default")
      (node (ref "Q14") (pin "3") (pinfunction "C_3") (pintype "passive"))
      (node (ref "Q15") (pin "1") (pinfunction "B_1") (pintype "passive"))
      (node (ref "R228") (pin "1") (pinfunction "1_1") (pintype "passive"))
      (node (ref "R232") (pin "1") (pinfunction "1_1") (pintype "passive"))
    )
    (net (code "50") (name "Net-(Q15-C)") (class "Default")
      (node (ref "LED4") (pin "2") (pinfunction "2_2") (pintype "passive"))
      (node (ref "Q15") (pin "3") (pinfunction "C_3") (pintype "passive"))
    )
    (net (code "51") (name "Net-(U36-AAM)") (class "Default")
      (node (ref "R213") (pin "2") (pinfunction "2_2") (pintype "passive"))
      (node (ref "R216") (pin "2") (pinfunction "2_2") (pintype "passive"))
      (node (ref "U36") (pin "1") (pinfunction "AAM_1") (pintype "passive"))
    )
    (net (code "52") (name "Net-(U36-BST)") (class "Default")
      (node (ref "R208") (pin "1") (pinfunction "1_1") (pintype "passive"))
      (node (ref "U36") (pin "5") (pinfunction "BST_5") (pintype "passive"))
    )
    (net (code "53") (name "Net-(U36-EN)") (class "Default")
      (node (ref "R207") (pin "1") (pinfunction "1_1") (pintype "passive"))
      (node (ref "R215") (pin "2") (pinfunction "2_2") (pintype "passive"))
      (node (ref "R249") (pin "1") (pinfunction "1_1") (pintype "passive"))
      (node (ref "U36") (pin "6") (pinfunction "EN_6") (pintype "passive"))
    )
    (net (code "54") (name "Net-(U36-FB)") (class "Default")
      (node (ref "R214") (pin "1") (pinfunction "1_1") (pintype "passive"))
      (node (ref "U36") (pin "8") (pinfunction "FB_8") (pintype "passive"))
    )
    (net (code "55") (name "Net-(U36-SW)") (class "Default")
      (node (ref "C229") (pin "2") (pinfunction "2_2") (pintype "passive"))
      (node (ref "L11") (pin "1") (pinfunction "1_1") (pintype "passive"))
      (node (ref "U36") (pin "3") (pinfunction "SW_3") (pintype "passive"))
    )
    (net (code "56") (name "Net-(U36-VCC)") (class "Default")
      (node (ref "C237") (pin "1") (pinfunction "1_1") (pintype "passive"))
      (node (ref "R213") (pin "1") (pinfunction "1_1") (pintype "passive"))
      (node (ref "U36") (pin "7") (pinfunction "VCC_7") (pintype "passive"))
    )
    (net (code "57") (name "Net-(U37-BS)") (class "Default")
      (node (ref "C231") (pin "2") (pinfunction "2_2") (pintype "passive"))
      (node (ref "U37") (pin "1") (pinfunction "BS_1") (pintype "passive"))
    )
    (net (code "58") (name "Net-(U37-EN)") (class "Default")
      (node (ref "C242") (pin "1") (pinfunction "1_1") (pintype "passive"))
      (node (ref "R211") (pin "1") (pinfunction "1_1") (pintype "passive"))
      (node (ref "R219") (pin "1") (pinfunction "1_1") (pintype "passive"))
      (node (ref "R256") (pin "1") (pinfunction "1_1") (pintype "passive"))
      (node (ref "U37") (pin "4") (pinfunction "EN_4") (pintype "passive"))
    )
    (net (code "59") (name "Net-(U37-SW)") (class "Default")
      (node (ref "C231") (pin "1") (pinfunction "1_1") (pintype "passive"))
      (node (ref "L12") (pin "1") (pinfunction "1_1") (pintype "passive"))
      (node (ref "U37") (pin "6") (pinfunction "SW_6") (pintype "passive"))
    )
    (net (code "60") (name "Net-(U37-VFB)") (class "Default")
      (node (ref "C239") (pin "1") (pinfunction "1_1") (pintype "passive"))
      (node (ref "R217") (pin "1") (pinfunction "1_1") (pintype "passive"))
      (node (ref "R220") (pin "2") (pinfunction "2_2") (pintype "passive"))
      (node (ref "U37") (pin "3") (pinfunction "VFB_3") (pintype "passive"))
    )
    (net (code "61") (name "PCIE_3V3") (class "Default")
      (node (ref "C233") (pin "2") (pinfunction "2_2") (pintype "passive"))
      (node (ref "C239") (pin "2") (pinfunction "2_2") (pintype "passive"))
      (node (ref "C240") (pin "2") (pinfunction "2_2") (pintype "passive"))
      (node (ref "C258") (pin "2") (pinfunction "2_2") (pintype "passive"))
      (node (ref "C259") (pin "2") (pinfunction "2_2") (pintype "passive"))
      (node (ref "C260") (pin "2") (pinfunction "2_2") (pintype "passive"))
      (node (ref "C261") (pin "2") (pinfunction "2_2") (pintype "passive"))
      (node (ref "C262") (pin "2") (pinfunction "2_2") (pintype "passive"))
      (node (ref "C263") (pin "2") (pinfunction "2_2") (pintype "passive"))
      (node (ref "J28") (pin "12") (pinfunction "3V3#7_12") (pintype "passive"))
      (node (ref "J28") (pin "14") (pinfunction "3V3#6_14") (pintype "passive"))
      (node (ref "J28") (pin "16") (pinfunction "3V3#5_16") (pintype "passive"))
      (node (ref "J28") (pin "18") (pinfunction "3V3#4_18") (pintype "passive"))
      (node (ref "J28") (pin "2") (pinfunction "3V3#9_2") (pintype "passive"))
      (node (ref "J28") (pin "4") (pinfunction "3V3#8_4") (pintype "passive"))
      (node (ref "J28") (pin "62") (pinfunction "3V3#3_62") (pintype "passive"))
      (node (ref "J28") (pin "64") (pinfunction "3V3#2_64") (pintype "passive"))
      (node (ref "J28") (pin "66") (pinfunction "3V3#1_66") (pintype "passive"))
      (node (ref "L12") (pin "2") (pinfunction "2_2") (pintype "passive"))
      (node (ref "R217") (pin "2") (pinfunction "2_2") (pintype "passive"))
      (node (ref "R224") (pin "2") (pinfunction "2_2") (pintype "passive"))
      (node (ref "R228") (pin "2") (pinfunction "2_2") (pintype "passive"))
      (node (ref "R229") (pin "2") (pinfunction "2_2") (pintype "passive"))
    )
    (net (code "62") (name "UIM_PWR") (class "Default")
      (node (ref "C264") (pin "2") (pinfunction "2_2") (pintype "passive"))
      (node (ref "C265") (pin "2") (pinfunction "2_2") (pintype "passive"))
      (node (ref "J27") (pin "8") (pinfunction "UIM_PWR_8") (pintype "passive"))
      (node (ref "J29") (pin "C1") (pinfunction "VCC_C1") (pintype "power_in"))
      (node (ref "R225") (pin "2") (pinfunction "2_2") (pintype "passive"))
      (node (ref "R226") (pin "2") (pinfunction "2_2") (pintype "passive"))
      (node (ref "R227") (pin "2") (pinfunction "2_2") (pintype "passive"))
    )
    (net (code "63") (name "VCC3V3_3G") (class "Default")
      (node (ref "C230") (pin "2") (pinfunction "2_2") (pintype "passive"))
      (node (ref "C232") (pin "2") (pinfunction "2_2") (pintype "passive"))
      (node (ref "C235") (pin "2") (pinfunction "2_2") (pintype "passive"))
      (node (ref "C238") (pin "2") (pinfunction "2_2") (pintype "passive"))
      (node (ref "C243") (pin "2") (pinfunction "2_2") (pintype "passive"))
      (node (ref "C244") (pin "2") (pinfunction "2_2") (pintype "passive"))
      (node (ref "C254") (pin "2") (pinfunction "2_2") (pintype "passive"))
      (node (ref "C255") (pin "2") (pinfunction "2_2") (pintype "passive"))
      (node (ref "C290") (pin "2") (pinfunction "2_2") (pintype "passive"))
      (node (ref "C291") (pin "2") (pinfunction "2_2") (pintype "passive"))
      (node (ref "C292") (pin "2") (pinfunction "2_2") (pintype "passive"))
      (node (ref "J27") (pin "2") (pinfunction "3.3V_AUX_2") (pintype "passive"))
      (node (ref "J27") (pin "39") (pinfunction "VCC_3V3_1_39") (pintype "passive"))
      (node (ref "J27") (pin "41") (pinfunction "VCC_3V3_2_41") (pintype "passive"))
      (node (ref "J27") (pin "52") (pinfunction "VCC_3V3_3_52") (pintype "passive"))
      (node (ref "L11") (pin "2") (pinfunction "2_2") (pintype "passive"))
      (node (ref "R210") (pin "2") (pinfunction "2_2") (pintype "passive"))
      (node (ref "R223") (pin "2") (pinfunction "2_2") (pintype "passive"))
    )
    (net (code "64") (name "VCC3V3_SYS") (class "Default")
      (node (ref "R207") (pin "2") (pinfunction "2_2") (pintype "passive"))
      (node (ref "R211") (pin "2") (pinfunction "2_2") (pintype "passive"))
    )
    (net (code "65") (name "unconnected-(J27-CN16-Pad57)") (class "Default")
      (node (ref "J27") (pin "57") (pinfunction "CN16_57") (pintype "passive"))
    )
    (net (code "66") (name "unconnected-(J27-LED_WWAN-Pad42)") (class "Default")
      (node (ref "J27") (pin "42") (pinfunction "LED_WWAN_42") (pintype "passive+no_connect"))
    )
    (net (code "67") (name "unconnected-(J27-NC1-Pad1)") (class "Default")
      (node (ref "J27") (pin "1") (pinfunction "NC1_1") (pintype "passive"))
    )
    (net (code "68") (name "unconnected-(J27-NC2-Pad3)") (class "Default")
      (node (ref "J27") (pin "3") (pinfunction "NC2_3") (pintype "passive"))
    )
    (net (code "69") (name "unconnected-(J27-NC3-Pad5)") (class "Default")
      (node (ref "J27") (pin "5") (pinfunction "NC3_5") (pintype "passive"))
    )
    (net (code "70") (name "unconnected-(J27-NC4-Pad7)") (class "Default")
      (node (ref "J27") (pin "7") (pinfunction "NC4_7") (pintype "passive"))
    )
    (net (code "71") (name "unconnected-(J27-NC5-Pad11)") (class "Default")
      (node (ref "J27") (pin "11") (pinfunction "NC5_11") (pintype "passive"))
    )
    (net (code "72") (name "unconnected-(J27-NC6-Pad6)") (class "Default")
      (node (ref "J27") (pin "6") (pinfunction "NC6_6") (pintype "passive"))
    )
    (net (code "73") (name "unconnected-(J27-NC7-Pad13)") (class "Default")
      (node (ref "J27") (pin "13") (pinfunction "NC7_13") (pintype "passive"))
    )
    (net (code "74") (name "unconnected-(J27-NC8-Pad17)") (class "Default")
      (node (ref "J27") (pin "17") (pinfunction "NC8_17") (pintype "passive"))
    )
    (net (code "75") (name "unconnected-(J27-NC9-Pad19)") (class "Default")
      (node (ref "J27") (pin "19") (pinfunction "NC9_19") (pintype "passive"))
    )
    (net (code "76") (name "unconnected-(J27-NC10-Pad23)") (class "Default")
      (node (ref "J27") (pin "23") (pinfunction "NC10_23") (pintype "passive"))
    )
    (net (code "77") (name "unconnected-(J27-NC11-Pad25)") (class "Default")
      (node (ref "J27") (pin "25") (pinfunction "NC11_25") (pintype "passive"))
    )
    (net (code "78") (name "unconnected-(J27-NC12-Pad31)") (class "Default")
      (node (ref "J27") (pin "31") (pinfunction "NC12_31") (pintype "passive"))
    )
    (net (code "79") (name "unconnected-(J27-NC13-Pad33)") (class "Default")
      (node (ref "J27") (pin "33") (pinfunction "NC13_33") (pintype "passive"))
    )
    (net (code "80") (name "unconnected-(J27-NC14-Pad55)") (class "Default")
      (node (ref "J27") (pin "55") (pinfunction "NC14_55") (pintype "passive"))
    )
    (net (code "81") (name "unconnected-(J27-NC15-Pad56)") (class "Default")
      (node (ref "J27") (pin "56") (pinfunction "NC15_56") (pintype "passive"))
    )
    (net (code "82") (name "unconnected-(J27-NC17-Pad59)") (class "Default")
      (node (ref "J27") (pin "59") (pinfunction "NC17_59") (pintype "passive"))
    )
    (net (code "83") (name "unconnected-(J27-NC18-Pad16)") (class "Default")
      (node (ref "J27") (pin "16") (pinfunction "NC18_16") (pintype "passive"))
    )
    (net (code "84") (name "unconnected-(J27-NC19-Pad24)") (class "Default")
      (node (ref "J27") (pin "24") (pinfunction "NC19_24") (pintype "passive"))
    )
    (net (code "85") (name "unconnected-(J27-NC20-Pad28)") (class "Default")
      (node (ref "J27") (pin "28") (pinfunction "NC20_28") (pintype "passive"))
    )
    (net (code "86") (name "unconnected-(J27-NC21-Pad30)") (class "Default")
      (node (ref "J27") (pin "30") (pinfunction "NC21_30") (pintype "passive"))
    )
    (net (code "87") (name "unconnected-(J27-NC22-Pad32)") (class "Default")
      (node (ref "J27") (pin "32") (pinfunction "NC22_32") (pintype "passive"))
    )
    (net (code "88") (name "unconnected-(J27-NC23-Pad44)") (class "Default")
      (node (ref "J27") (pin "44") (pinfunction "NC23_44") (pintype "passive"))
    )
    (net (code "89") (name "unconnected-(J27-NC24-Pad46)") (class "Default")
      (node (ref "J27") (pin "46") (pinfunction "NC24_46") (pintype "passive"))
    )
    (net (code "90") (name "unconnected-(J27-NC25-Pad48)") (class "Default")
      (node (ref "J27") (pin "48") (pinfunction "NC25_48") (pintype "passive"))
    )
    (net (code "91") (name "unconnected-(J27-PCM_CLK-Pad45)") (class "Default")
      (node (ref "J27") (pin "45") (pinfunction "PCM_CLK_45") (pintype "passive+no_connect"))
    )
    (net (code "92") (name "unconnected-(J27-PCM_DIN-Pad49)") (class "Default")
      (node (ref "J27") (pin "49") (pinfunction "PCM_DIN_49") (pintype "passive+no_connect"))
    )
    (net (code "93") (name "unconnected-(J27-PCM_DOUT-Pad47)") (class "Default")
      (node (ref "J27") (pin "47") (pinfunction "PCM_DOUT_47") (pintype "passive+no_connect"))
    )
    (net (code "94") (name "unconnected-(J27-PCM_SYNC-Pad51)") (class "Default")
      (node (ref "J27") (pin "51") (pinfunction "PCM_SYNC_51") (pintype "passive+no_connect"))
    )
    (net (code "95") (name "unconnected-(J27-W_DISABLE_N-Pad20)") (class "Default")
      (node (ref "J27") (pin "20") (pinfunction "W_DISABLE_N_20") (pintype "passive+no_connect"))
    )
    (net (code "96") (name "unconnected-(J28-G3-Pad71)") (class "Default")
      (node (ref "J28") (pin "71") (pinfunction "G3_71") (pintype "passive+no_connect"))
    )
    (net (code "97") (name "unconnected-(J28-G4-Pad72)") (class "Default")
      (node (ref "J28") (pin "72") (pinfunction "G4_72") (pintype "passive+no_connect"))
    )
    (net (code "98") (name "unconnected-(J28-G5-Pad73)") (class "Default")
      (node (ref "J28") (pin "73") (pinfunction "G5_73") (pintype "passive"))
    )
    (net (code "99") (name "unconnected-(J28-G6-Pad74)") (class "Default")
      (node (ref "J28") (pin "74") (pinfunction "G6_74") (pintype "passive"))
    )
    (net (code "100") (name "unconnected-(J28-G7-Pad70)") (class "Default")
      (node (ref "J28") (pin "70") (pinfunction "G7_70") (pintype "passive"))
    )
    (net (code "101") (name "unconnected-(J28-NC-PCIE{slash}GND-SATA-Pad61)") (class "Default")
      (node (ref "J28") (pin "61") (pinfunction "NC-PCIE/GND-SATA_61") (pintype "passive+no_connect"))
    )
    (net (code "102") (name "unconnected-(J28-NC1-Pad59)") (class "Default")
      (node (ref "J28") (pin "59") (pinfunction "NC1_59") (pintype "passive"))
    )
    (net (code "103") (name "unconnected-(J28-NC2-Pad58)") (class "Default")
      (node (ref "J28") (pin "58") (pinfunction "NC2_58") (pintype "passive"))
    )
    (net (code "104") (name "unconnected-(J28-NC3-Pad56)") (class "Default")
      (node (ref "J28") (pin "56") (pinfunction "NC3_56") (pintype "passive"))
    )
    (net (code "105") (name "unconnected-(J28-NC4-Pad46)") (class "Default")
      (node (ref "J28") (pin "46") (pinfunction "NC4_46") (pintype "passive"))
    )
    (net (code "106") (name "unconnected-(J28-NC5-Pad44)") (class "Default")
      (node (ref "J28") (pin "44") (pinfunction "NC5_44") (pintype "passive"))
    )
    (net (code "107") (name "unconnected-(J28-NC6-Pad42)") (class "Default")
      (node (ref "J28") (pin "42") (pinfunction "NC6_42") (pintype "passive"))
    )
    (net (code "108") (name "unconnected-(J28-NC7-Pad40)") (class "Default")
      (node (ref "J28") (pin "40") (pinfunction "NC7_40") (pintype "passive"))
    )
    (net (code "109") (name "unconnected-(J28-NC8-Pad36)") (class "Default")
      (node (ref "J28") (pin "36") (pinfunction "NC8_36") (pintype "passive"))
    )
    (net (code "110") (name "unconnected-(J28-NC9-Pad34)") (class "Default")
      (node (ref "J28") (pin "34") (pinfunction "NC9_34") (pintype "passive"))
    )
    (net (code "111") (name "unconnected-(J28-NC10-Pad32)") (class "Default")
      (node (ref "J28") (pin "32") (pinfunction "NC10_32") (pintype "passive"))
    )
    (net (code "112") (name "unconnected-(J28-NC11-Pad30)") (class "Default")
      (node (ref "J28") (pin "30") (pinfunction "NC11_30") (pintype "passive"))
    )
    (net (code "113") (name "unconnected-(J28-NC12-Pad28)") (class "Default")
      (node (ref "J28") (pin "28") (pinfunction "NC12_28") (pintype "passive"))
    )
    (net (code "114") (name "unconnected-(J28-NC13-Pad26)") (class "Default")
      (node (ref "J28") (pin "26") (pinfunction "NC13_26") (pintype "passive"))
    )
    (net (code "115") (name "unconnected-(J28-NC14-Pad24)") (class "Default")
      (node (ref "J28") (pin "24") (pinfunction "NC14_24") (pintype "passive"))
    )
    (net (code "116") (name "unconnected-(J28-NC15-Pad22)") (class "Default")
      (node (ref "J28") (pin "22") (pinfunction "NC15_22") (pintype "passive"))
    )
    (net (code "117") (name "unconnected-(J28-NC16-Pad20)") (class "Default")
      (node (ref "J28") (pin "20") (pinfunction "NC16_20") (pintype "passive"))
    )
    (net (code "118") (name "unconnected-(J28-NC17-Pad8)") (class "Default")
      (node (ref "J28") (pin "8") (pinfunction "NC17_8") (pintype "passive"))
    )
    (net (code "119") (name "unconnected-(J28-NC18-Pad6)") (class "Default")
      (node (ref "J28") (pin "6") (pinfunction "NC18_6") (pintype "passive"))
    )
    (net (code "120") (name "unconnected-(J28-NC21-Pad48)") (class "Default")
      (node (ref "J28") (pin "48") (pinfunction "NC21_48") (pintype "passive"))
    )
    (net (code "121") (name "unconnected-(J29-VPP-PadC6)") (class "Default")
      (node (ref "J29") (pin "C6") (pinfunction "VPP_C6") (pintype "power_in+no_connect"))
    )
  )
)
